# PR9001.net
KiCad netlist of a schematic drawn in EAGLE
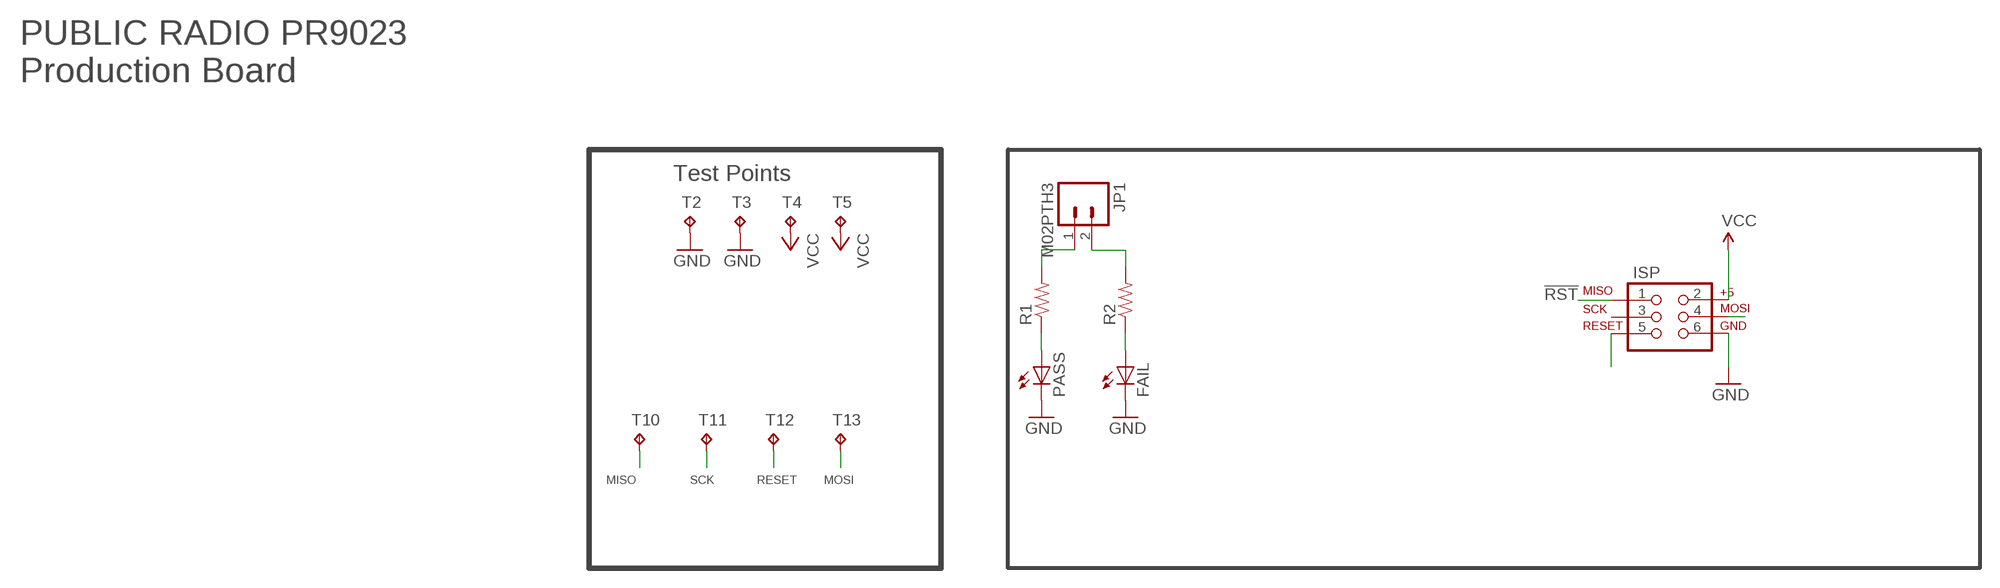
[diagram p0: schematic, sheet 1]

(export (version "E")
  (design (tool "Eeschema 10.0.6"))
  (components
    (comp (ref "FAIL")
      (value "LED5MM")
      (footprint "eagle-import:LED5MM")
      (libsource (lib "eagle-import") (part "LED5MM"))
    )
    (comp (ref "ISP")
      (value "AVR_SPI_PRG_6NS")
      (footprint "eagle-import:2X3-NS")
      (libsource (lib "eagle-import") (part "AVR_SPI_PRG_6NS"))
    )
    (comp (ref "JP1")
      (value "M02PTH3")
      (footprint "eagle-import:1X02_LONGPADS")
      (libsource (lib "eagle-import") (part "M02PTH3"))
    )
    (comp (ref "PASS")
      (value "LED5MM")
      (footprint "eagle-import:LED5MM")
      (libsource (lib "eagle-import") (part "LED5MM"))
    )
    (comp (ref "R1")
      (value "RESISTORPTH-1/4W-VERT")
      (footprint "eagle-import:AXIAL-0.1")
      (libsource (lib "eagle-import") (part "RESISTORPTH-1/4W-VERT"))
    )
    (comp (ref "R2")
      (value "RESISTORPTH-1/4W-VERT")
      (footprint "eagle-import:AXIAL-0.1")
      (libsource (lib "eagle-import") (part "RESISTORPTH-1/4W-VERT"))
    )
    (comp (ref "T2")
      (value "PR9001_TESTPOINT")
      (footprint "eagle-import:PR9001_TESTPOINT")
      (libsource (lib "eagle-import") (part "PR9001_TESTPOINT"))
    )
    (comp (ref "T3")
      (value "PR9001_TESTPOINT")
      (footprint "eagle-import:PR9001_TESTPOINT")
      (libsource (lib "eagle-import") (part "PR9001_TESTPOINT"))
    )
    (comp (ref "T4")
      (value "PR9001_TESTPOINT")
      (footprint "eagle-import:PR9001_TESTPOINT")
      (libsource (lib "eagle-import") (part "PR9001_TESTPOINT"))
    )
    (comp (ref "T5")
      (value "PR9001_TESTPOINT")
      (footprint "eagle-import:PR9001_TESTPOINT")
      (libsource (lib "eagle-import") (part "PR9001_TESTPOINT"))
    )
    (comp (ref "T10")
      (value "PR9001_TESTPOINT")
      (footprint "eagle-import:PR9001_TESTPOINT")
      (libsource (lib "eagle-import") (part "PR9001_TESTPOINT"))
    )
    (comp (ref "T11")
      (value "PR9001_TESTPOINT")
      (footprint "eagle-import:PR9001_TESTPOINT")
      (libsource (lib "eagle-import") (part "PR9001_TESTPOINT"))
    )
    (comp (ref "T12")
      (value "PR9001_TESTPOINT")
      (footprint "eagle-import:PR9001_TESTPOINT")
      (libsource (lib "eagle-import") (part "PR9001_TESTPOINT"))
    )
    (comp (ref "T13")
      (value "PR9001_TESTPOINT")
      (footprint "eagle-import:PR9001_TESTPOINT")
      (libsource (lib "eagle-import") (part "PR9001_TESTPOINT"))
    )
  )
  (nets
    (net (code "1") (name "/RESET") (class "Default")
      (node (ref "ISP") (pin "5") (pinfunction "5_5") (pintype "passive"))
      (node (ref "T12") (pin "P$1") (pinfunction "TP_P$1") (pintype "input"))
    )
    (net (code "2") (name "/SDIO") (class "Default")
      (node (ref "ISP") (pin "4") (pinfunction "4_4") (pintype "passive"))
      (node (ref "T13") (pin "P$1") (pinfunction "TP_P$1") (pintype "input"))
    )
    (net (code "3") (name "/~{RST}") (class "Default")
      (node (ref "ISP") (pin "1") (pinfunction "1_1") (pintype "passive"))
      (node (ref "T10") (pin "P$1") (pinfunction "TP_P$1") (pintype "input"))
    )
    (net (code "4") (name "GND") (class "Default")
      (node (ref "FAIL") (pin "K") (pinfunction "C_K") (pintype "passive"))
      (node (ref "ISP") (pin "6") (pinfunction "6_6") (pintype "passive"))
      (node (ref "PASS") (pin "K") (pinfunction "C_K") (pintype "passive"))
      (node (ref "T2") (pin "P$1") (pinfunction "TP_P$1") (pintype "input"))
      (node (ref "T3") (pin "P$1") (pinfunction "TP_P$1") (pintype "input"))
    )
    (net (code "5") (name "Net-(R1-1)") (class "Default")
      (node (ref "PASS") (pin "A") (pinfunction "A_A") (pintype "passive"))
      (node (ref "R1") (pin "P$1") (pinfunction "1_P$1") (pintype "passive"))
    )
    (net (code "6") (name "Net-(R1-2)") (class "Default")
      (node (ref "JP1") (pin "1") (pinfunction "1_1") (pintype "passive"))
      (node (ref "R1") (pin "P$2") (pinfunction "2_P$2") (pintype "passive"))
    )
    (net (code "7") (name "Net-(R2-1)") (class "Default")
      (node (ref "FAIL") (pin "A") (pinfunction "A_A") (pintype "passive"))
      (node (ref "R2") (pin "P$1") (pinfunction "1_P$1") (pintype "passive"))
    )
    (net (code "8") (name "Net-(R2-2)") (class "Default")
      (node (ref "JP1") (pin "2") (pinfunction "2_2") (pintype "passive"))
      (node (ref "R2") (pin "P$2") (pinfunction "2_P$2") (pintype "passive"))
    )
    (net (code "9") (name "VCC") (class "Default")
      (node (ref "ISP") (pin "2") (pinfunction "2_2") (pintype "passive"))
      (node (ref "T4") (pin "P$1") (pinfunction "TP_P$1") (pintype "input"))
      (node (ref "T5") (pin "P$1") (pinfunction "TP_P$1") (pintype "input"))
    )
    (net (code "10") (name "unconnected-(ISP-Pad3)") (class "Default")
      (node (ref "ISP") (pin "3") (pinfunction "3_3") (pintype "passive"))
    )
    (net (code "11") (name "unconnected-(T11-TP-PadP$1)") (class "Default")
      (node (ref "T11") (pin "P$1") (pinfunction "TP_P$1") (pintype "input"))
    )
  )
)
